# jt-100.net
KiCad netlist of a schematic drawn in EAGLE
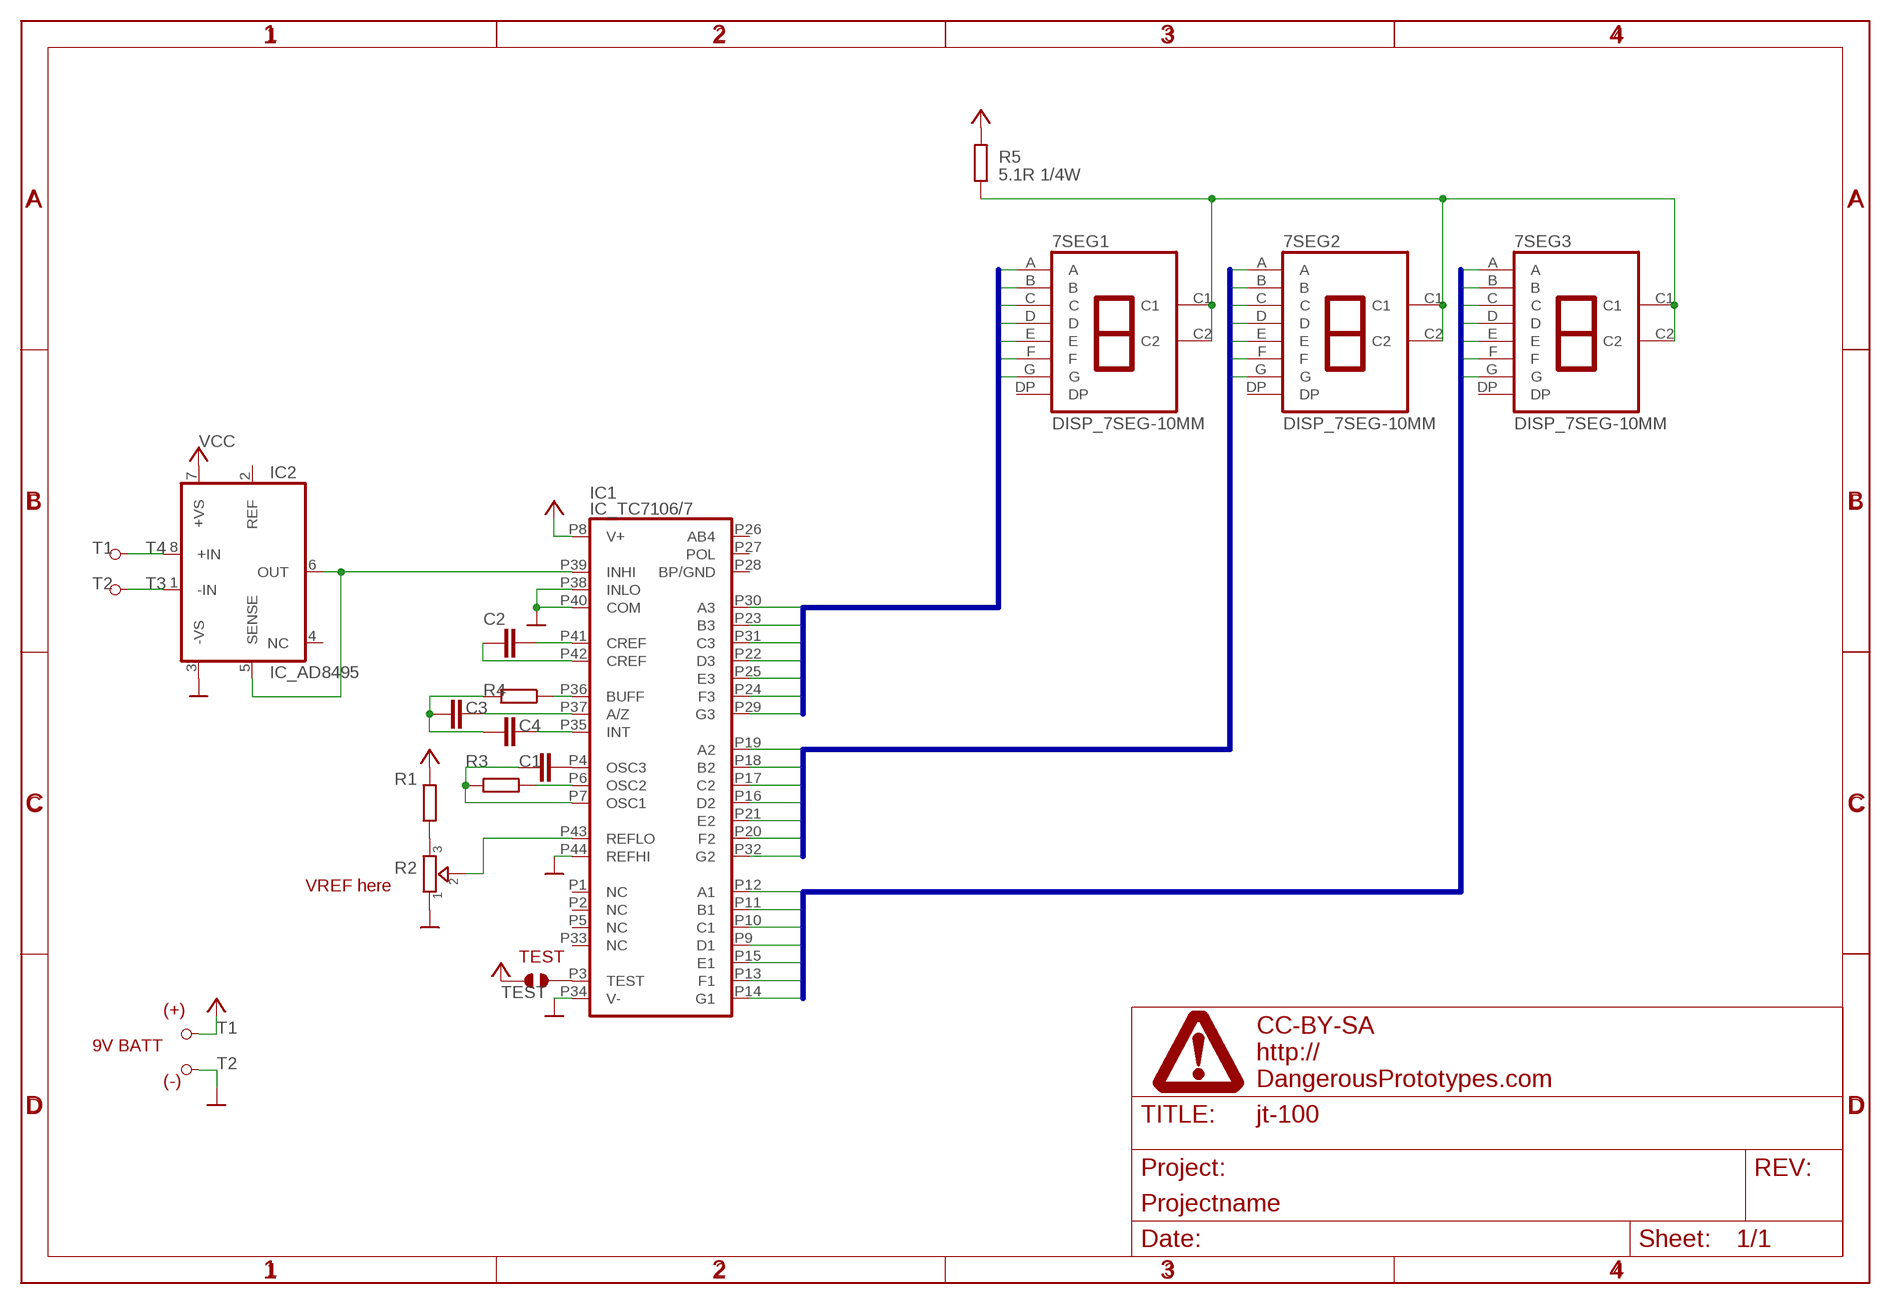
[diagram p0: schematic, sheet 1]

(export (version "E")
  (design (tool "Eeschema 10.0.6"))
  (components
    (comp (ref "7SEG1")
      (value "DISP_7SEG-10MM")
      (footprint "eagle-import:DISP_7SEG_KTS_4817CKR-P")
      (libsource (lib "eagle-import") (part "DISP_7SEG-10MM"))
    )
    (comp (ref "7SEG2")
      (value "DISP_7SEG-10MM")
      (footprint "eagle-import:DISP_7SEG_KTS_4817CKR-P")
      (libsource (lib "eagle-import") (part "DISP_7SEG-10MM"))
    )
    (comp (ref "7SEG3")
      (value "DISP_7SEG-10MM")
      (footprint "eagle-import:DISP_7SEG_KTS_4817CKR-P")
      (libsource (lib "eagle-import") (part "DISP_7SEG-10MM"))
    )
    (comp (ref "C1")
      (value "CAPACITOR_NPOL-1206")
      (footprint "eagle-import:C1206")
      (libsource (lib "eagle-import") (part "CAPACITOR_NPOL-1206"))
    )
    (comp (ref "C2")
      (value "CAPACITOR_NPOL-1206")
      (footprint "eagle-import:C1206")
      (libsource (lib "eagle-import") (part "CAPACITOR_NPOL-1206"))
    )
    (comp (ref "C3")
      (value "CAPACITOR_NPOL-1206")
      (footprint "eagle-import:C1206")
      (libsource (lib "eagle-import") (part "CAPACITOR_NPOL-1206"))
    )
    (comp (ref "C4")
      (value "CAPACITOR_NPOL-1206")
      (footprint "eagle-import:C1206")
      (libsource (lib "eagle-import") (part "CAPACITOR_NPOL-1206"))
    )
    (comp (ref "IC1")
      (value "IC_TC7106/7")
      (footprint "eagle-import:TQFP-44")
      (libsource (lib "eagle-import") (part "IC_TC7106/7"))
    )
    (comp (ref "IC2")
      (value "IC_AD8495")
      (footprint "eagle-import:MSOP8")
      (libsource (lib "eagle-import") (part "IC_AD8495"))
    )
    (comp (ref "R1")
      (value "RESISTOR-1206")
      (footprint "eagle-import:R1206")
      (libsource (lib "eagle-import") (part "RESISTOR-1206"))
    )
    (comp (ref "R2")
      (value "TRIMMER-3314G")
      (footprint "eagle-import:TRIMMER_3314G")
      (libsource (lib "eagle-import") (part "TRIMMER-3314G"))
    )
    (comp (ref "R3")
      (value "RESISTOR-1206")
      (footprint "eagle-import:R1206")
      (libsource (lib "eagle-import") (part "RESISTOR-1206"))
    )
    (comp (ref "R4")
      (value "RESISTOR-1206")
      (footprint "eagle-import:R1206")
      (libsource (lib "eagle-import") (part "RESISTOR-1206"))
    )
    (comp (ref "R5")
      (value "5.1R 1/4W")
      (footprint "eagle-import:R1206")
      (libsource (lib "eagle-import") (part "RESISTOR-1206"))
    )
    (comp (ref "T1")
      (value "PAD_TERMINAL-1.02MM_SQUARE")
      (footprint "eagle-import:CON_PAD_SQUARE_1.02MM")
      (libsource (lib "eagle-import") (part "PAD_TERMINAL-1.02MM_SQUARE"))
    )
    (comp (ref "T2")
      (value "PAD_TERMINAL-1.02MM_ROUND")
      (footprint "eagle-import:CON_PAD_ROUND_1.02MM")
      (libsource (lib "eagle-import") (part "PAD_TERMINAL-1.02MM_ROUND"))
    )
    (comp (ref "T3")
      (value "PAD_TERMINAL-1.02MM_ROUND")
      (footprint "eagle-import:CON_PAD_ROUND_1.02MM")
      (libsource (lib "eagle-import") (part "PAD_TERMINAL-1.02MM_ROUND"))
    )
    (comp (ref "T4")
      (value "PAD_TERMINAL-1.02MM_ROUND")
      (footprint "eagle-import:CON_PAD_ROUND_1.02MM")
      (libsource (lib "eagle-import") (part "PAD_TERMINAL-1.02MM_ROUND"))
    )
    (comp (ref "TEST")
      (value "JUMPER_SOLDER_1X2")
      (footprint "eagle-import:JUMPER_SOLDER_1X2")
      (libsource (lib "eagle-import") (part "JUMPER_SOLDER_1X2"))
    )
    (comp (ref "U$1")
      (value "FRAME_DINA4_L")
      (footprint "eagle-import:DP_LOGO")
      (libsource (lib "eagle-import") (part "FRAME_DINA4_L"))
    )
  )
  (nets
    (net (code "1") (name "/1S1") (class "Default")
      (node (ref "7SEG3") (pin "A") (pinfunction "A_A") (pintype "bidirectional"))
      (node (ref "IC1") (pin "P12") (pinfunction "A1_P12") (pintype "bidirectional"))
    )
    (net (code "2") (name "/1S2") (class "Default")
      (node (ref "7SEG3") (pin "B") (pinfunction "B_B") (pintype "bidirectional"))
      (node (ref "IC1") (pin "P11") (pinfunction "B1_P11") (pintype "bidirectional"))
    )
    (net (code "3") (name "/1S3") (class "Default")
      (node (ref "7SEG3") (pin "C") (pinfunction "C_C") (pintype "bidirectional"))
      (node (ref "IC1") (pin "P10") (pinfunction "C1_P10") (pintype "bidirectional"))
    )
    (net (code "4") (name "/1S4") (class "Default")
      (node (ref "7SEG3") (pin "D") (pinfunction "D_D") (pintype "bidirectional"))
      (node (ref "IC1") (pin "P9") (pinfunction "D1_P9") (pintype "bidirectional"))
    )
    (net (code "5") (name "/1S5") (class "Default")
      (node (ref "7SEG3") (pin "E") (pinfunction "E_E") (pintype "bidirectional"))
      (node (ref "IC1") (pin "P15") (pinfunction "E1_P15") (pintype "bidirectional"))
    )
    (net (code "6") (name "/1S6") (class "Default")
      (node (ref "7SEG3") (pin "F") (pinfunction "F_F") (pintype "bidirectional"))
      (node (ref "IC1") (pin "P13") (pinfunction "F1_P13") (pintype "bidirectional"))
    )
    (net (code "7") (name "/1S7") (class "Default")
      (node (ref "7SEG3") (pin "G") (pinfunction "G_G") (pintype "bidirectional"))
      (node (ref "IC1") (pin "P14") (pinfunction "G1_P14") (pintype "bidirectional"))
    )
    (net (code "8") (name "/10S1") (class "Default")
      (node (ref "7SEG2") (pin "A") (pinfunction "A_A") (pintype "bidirectional"))
      (node (ref "IC1") (pin "P19") (pinfunction "A2_P19") (pintype "input"))
    )
    (net (code "9") (name "/10S2") (class "Default")
      (node (ref "7SEG2") (pin "B") (pinfunction "B_B") (pintype "bidirectional"))
      (node (ref "IC1") (pin "P18") (pinfunction "B2_P18") (pintype "input"))
    )
    (net (code "10") (name "/10S3") (class "Default")
      (node (ref "7SEG2") (pin "C") (pinfunction "C_C") (pintype "bidirectional"))
      (node (ref "IC1") (pin "P17") (pinfunction "C2_P17") (pintype "input"))
    )
    (net (code "11") (name "/10S4") (class "Default")
      (node (ref "7SEG2") (pin "D") (pinfunction "D_D") (pintype "bidirectional"))
      (node (ref "IC1") (pin "P16") (pinfunction "D2_P16") (pintype "bidirectional"))
    )
    (net (code "12") (name "/10S5") (class "Default")
      (node (ref "7SEG2") (pin "E") (pinfunction "E_E") (pintype "bidirectional"))
      (node (ref "IC1") (pin "P21") (pinfunction "E2_P21") (pintype "input"))
    )
    (net (code "13") (name "/10S6") (class "Default")
      (node (ref "7SEG2") (pin "F") (pinfunction "F_F") (pintype "bidirectional"))
      (node (ref "IC1") (pin "P20") (pinfunction "F2_P20") (pintype "input"))
    )
    (net (code "14") (name "/10S7") (class "Default")
      (node (ref "7SEG2") (pin "G") (pinfunction "G_G") (pintype "bidirectional"))
      (node (ref "IC1") (pin "P32") (pinfunction "G2_P32") (pintype "input"))
    )
    (net (code "15") (name "/100S1") (class "Default")
      (node (ref "7SEG1") (pin "A") (pinfunction "A_A") (pintype "bidirectional"))
      (node (ref "IC1") (pin "P30") (pinfunction "A3_P30") (pintype "input"))
    )
    (net (code "16") (name "/100S2") (class "Default")
      (node (ref "7SEG1") (pin "B") (pinfunction "B_B") (pintype "bidirectional"))
      (node (ref "IC1") (pin "P23") (pinfunction "B3_P23") (pintype "input"))
    )
    (net (code "17") (name "/100S3") (class "Default")
      (node (ref "7SEG1") (pin "C") (pinfunction "C_C") (pintype "bidirectional"))
      (node (ref "IC1") (pin "P31") (pinfunction "C3_P31") (pintype "input"))
    )
    (net (code "18") (name "/100S4") (class "Default")
      (node (ref "7SEG1") (pin "D") (pinfunction "D_D") (pintype "bidirectional"))
      (node (ref "IC1") (pin "P22") (pinfunction "D3_P22") (pintype "input"))
    )
    (net (code "19") (name "/100S5") (class "Default")
      (node (ref "7SEG1") (pin "E") (pinfunction "E_E") (pintype "bidirectional"))
      (node (ref "IC1") (pin "P25") (pinfunction "E3_P25") (pintype "input"))
    )
    (net (code "20") (name "/100S6") (class "Default")
      (node (ref "7SEG1") (pin "F") (pinfunction "F_F") (pintype "bidirectional"))
      (node (ref "IC1") (pin "P24") (pinfunction "F3_P24") (pintype "input"))
    )
    (net (code "21") (name "/100S7") (class "Default")
      (node (ref "7SEG1") (pin "G") (pinfunction "G_G") (pintype "bidirectional"))
      (node (ref "IC1") (pin "P29") (pinfunction "G3_P29") (pintype "input"))
    )
    (net (code "22") (name "/T1") (class "Default")
      (node (ref "IC2") (pin "8") (pinfunction "+IN_8") (pintype "input"))
      (node (ref "T4") (pin "P") (pinfunction "P_P") (pintype "passive"))
    )
    (net (code "23") (name "/T2") (class "Default")
      (node (ref "IC2") (pin "1") (pinfunction "-IN_1") (pintype "input"))
      (node (ref "T3") (pin "P") (pinfunction "P_P") (pintype "passive"))
    )
    (net (code "24") (name "Net-(7SEG1-PadC1)") (class "Default")
      (node (ref "7SEG1") (pin "C1") (pinfunction "C1_C1") (pintype "bidirectional"))
      (node (ref "7SEG1") (pin "C2") (pinfunction "C2_C2") (pintype "bidirectional"))
      (node (ref "7SEG2") (pin "C1") (pinfunction "C1_C1") (pintype "bidirectional"))
      (node (ref "7SEG2") (pin "C2") (pinfunction "C2_C2") (pintype "bidirectional"))
      (node (ref "7SEG3") (pin "C1") (pinfunction "C1_C1") (pintype "bidirectional"))
      (node (ref "7SEG3") (pin "C2") (pinfunction "C2_C2") (pintype "bidirectional"))
      (node (ref "R5") (pin "1") (pinfunction "1_1") (pintype "passive"))
    )
    (net (code "25") (name "Net-(C2-Pad1)") (class "Default")
      (node (ref "C2") (pin "1") (pinfunction "1_1") (pintype "passive"))
      (node (ref "IC1") (pin "P42") (pinfunction "CREF_P42") (pintype "input"))
    )
    (net (code "26") (name "Net-(C2-Pad2)") (class "Default")
      (node (ref "C2") (pin "2") (pinfunction "2_2") (pintype "passive"))
      (node (ref "IC1") (pin "P41") (pinfunction "CREF_P41") (pintype "input"))
    )
    (net (code "27") (name "Net-(C3-Pad1)") (class "Default")
      (node (ref "C3") (pin "1") (pinfunction "1_1") (pintype "passive"))
      (node (ref "C4") (pin "1") (pinfunction "1_1") (pintype "passive"))
      (node (ref "R4") (pin "2") (pinfunction "2_2") (pintype "passive"))
    )
    (net (code "28") (name "Net-(IC1-A{slash}Z)") (class "Default")
      (node (ref "C3") (pin "2") (pinfunction "2_2") (pintype "passive"))
      (node (ref "IC1") (pin "P37") (pinfunction "A/Z_P37") (pintype "input"))
    )
    (net (code "29") (name "Net-(IC1-BUFF)") (class "Default")
      (node (ref "IC1") (pin "P36") (pinfunction "BUFF_P36") (pintype "input"))
      (node (ref "R4") (pin "1") (pinfunction "1_1") (pintype "passive"))
    )
    (net (code "30") (name "Net-(IC1-INHI)") (class "Default")
      (node (ref "IC1") (pin "P39") (pinfunction "INHI_P39") (pintype "input"))
      (node (ref "IC2") (pin "5") (pinfunction "SENSE_5") (pintype "bidirectional"))
      (node (ref "IC2") (pin "6") (pinfunction "OUT_6") (pintype "output"))
    )
    (net (code "31") (name "Net-(IC1-INT)") (class "Default")
      (node (ref "C4") (pin "2") (pinfunction "2_2") (pintype "passive"))
      (node (ref "IC1") (pin "P35") (pinfunction "INT_P35") (pintype "input"))
    )
    (net (code "32") (name "Net-(IC1-OSC1)") (class "Default")
      (node (ref "C1") (pin "1") (pinfunction "1_1") (pintype "passive"))
      (node (ref "IC1") (pin "P7") (pinfunction "OSC1_P7") (pintype "bidirectional"))
      (node (ref "R3") (pin "2") (pinfunction "2_2") (pintype "passive"))
    )
    (net (code "33") (name "Net-(IC1-OSC2)") (class "Default")
      (node (ref "IC1") (pin "P6") (pinfunction "OSC2_P6") (pintype "bidirectional"))
      (node (ref "R3") (pin "1") (pinfunction "1_1") (pintype "passive"))
    )
    (net (code "34") (name "Net-(IC1-OSC3)") (class "Default")
      (node (ref "C1") (pin "2") (pinfunction "2_2") (pintype "passive"))
      (node (ref "IC1") (pin "P4") (pinfunction "OSC3_P4") (pintype "bidirectional"))
    )
    (net (code "35") (name "Net-(IC1-REFLO)") (class "Default")
      (node (ref "IC1") (pin "P43") (pinfunction "REFLO_P43") (pintype "input"))
      (node (ref "R2") (pin "2") (pinfunction "2_2") (pintype "passive"))
    )
    (net (code "36") (name "Net-(IC1-TEST)") (class "Default")
      (node (ref "IC1") (pin "P3") (pinfunction "TEST_P3") (pintype "bidirectional"))
      (node (ref "TEST") (pin "2") (pinfunction "2_2") (pintype "passive"))
    )
    (net (code "37") (name "Net-(R1-Pad1)") (class "Default")
      (node (ref "R1") (pin "1") (pinfunction "1_1") (pintype "passive"))
      (node (ref "R2") (pin "3") (pinfunction "3_3") (pintype "passive"))
    )
    (net (code "38") (name "SUPPLY_GND") (class "Default")
      (node (ref "IC1") (pin "P34") (pinfunction "V-_P34") (pintype "power_in"))
      (node (ref "IC1") (pin "P38") (pinfunction "INLO_P38") (pintype "input"))
      (node (ref "IC1") (pin "P40") (pinfunction "COM_P40") (pintype "input"))
      (node (ref "IC1") (pin "P44") (pinfunction "REFHI_P44") (pintype "input"))
      (node (ref "IC2") (pin "3") (pinfunction "-VS_3") (pintype "power_in"))
      (node (ref "R2") (pin "1") (pinfunction "1_1") (pintype "passive"))
      (node (ref "T2") (pin "P") (pinfunction "P_P") (pintype "passive"))
    )
    (net (code "39") (name "SUPPLY_VCC") (class "Default")
      (node (ref "IC1") (pin "P8") (pinfunction "V+_P8") (pintype "power_in"))
      (node (ref "IC2") (pin "7") (pinfunction "+VS_7") (pintype "power_in"))
      (node (ref "R1") (pin "2") (pinfunction "2_2") (pintype "passive"))
      (node (ref "R5") (pin "2") (pinfunction "2_2") (pintype "passive"))
      (node (ref "T1") (pin "P") (pinfunction "P_P") (pintype "passive"))
      (node (ref "TEST") (pin "1") (pinfunction "1_1") (pintype "passive"))
    )
    (net (code "40") (name "unconnected-(7SEG1-PadDP)") (class "Default")
      (node (ref "7SEG1") (pin "DP") (pinfunction "DP_DP") (pintype "bidirectional"))
    )
    (net (code "41") (name "unconnected-(7SEG2-PadDP)") (class "Default")
      (node (ref "7SEG2") (pin "DP") (pinfunction "DP_DP") (pintype "bidirectional"))
    )
    (net (code "42") (name "unconnected-(7SEG3-PadDP)") (class "Default")
      (node (ref "7SEG3") (pin "DP") (pinfunction "DP_DP") (pintype "bidirectional"))
    )
    (net (code "43") (name "unconnected-(IC1-AB4-PadP26)") (class "Default")
      (node (ref "IC1") (pin "P26") (pinfunction "AB4_P26") (pintype "input"))
    )
    (net (code "44") (name "unconnected-(IC1-BP{slash}GND-PadP28)") (class "Default")
      (node (ref "IC1") (pin "P28") (pinfunction "BP/GND_P28") (pintype "input"))
    )
    (net (code "45") (name "unconnected-(IC1-NC-PadP1)") (class "Default")
      (node (ref "IC1") (pin "P1") (pinfunction "NC_P1") (pintype "bidirectional"))
    )
    (net (code "46") (name "unconnected-(IC1-NC-PadP2)") (class "Default")
      (node (ref "IC1") (pin "P2") (pinfunction "NC_P2") (pintype "bidirectional"))
    )
    (net (code "47") (name "unconnected-(IC1-NC-PadP5)") (class "Default")
      (node (ref "IC1") (pin "P5") (pinfunction "NC_P5") (pintype "bidirectional"))
    )
    (net (code "48") (name "unconnected-(IC1-NC-PadP33)") (class "Default")
      (node (ref "IC1") (pin "P33") (pinfunction "NC_P33") (pintype "input"))
    )
    (net (code "49") (name "unconnected-(IC1-POL-PadP27)") (class "Default")
      (node (ref "IC1") (pin "P27") (pinfunction "POL_P27") (pintype "input"))
    )
    (net (code "50") (name "unconnected-(IC2-NC-Pad4)") (class "Default")
      (node (ref "IC2") (pin "4") (pinfunction "NC_4") (pintype "bidirectional"))
    )
    (net (code "51") (name "unconnected-(IC2-REF-Pad2)") (class "Default")
      (node (ref "IC2") (pin "2") (pinfunction "REF_2") (pintype "bidirectional"))
    )
  )
)
